# Sheet1.net
KiCad netlist of a schematic drawn in Altium Designer
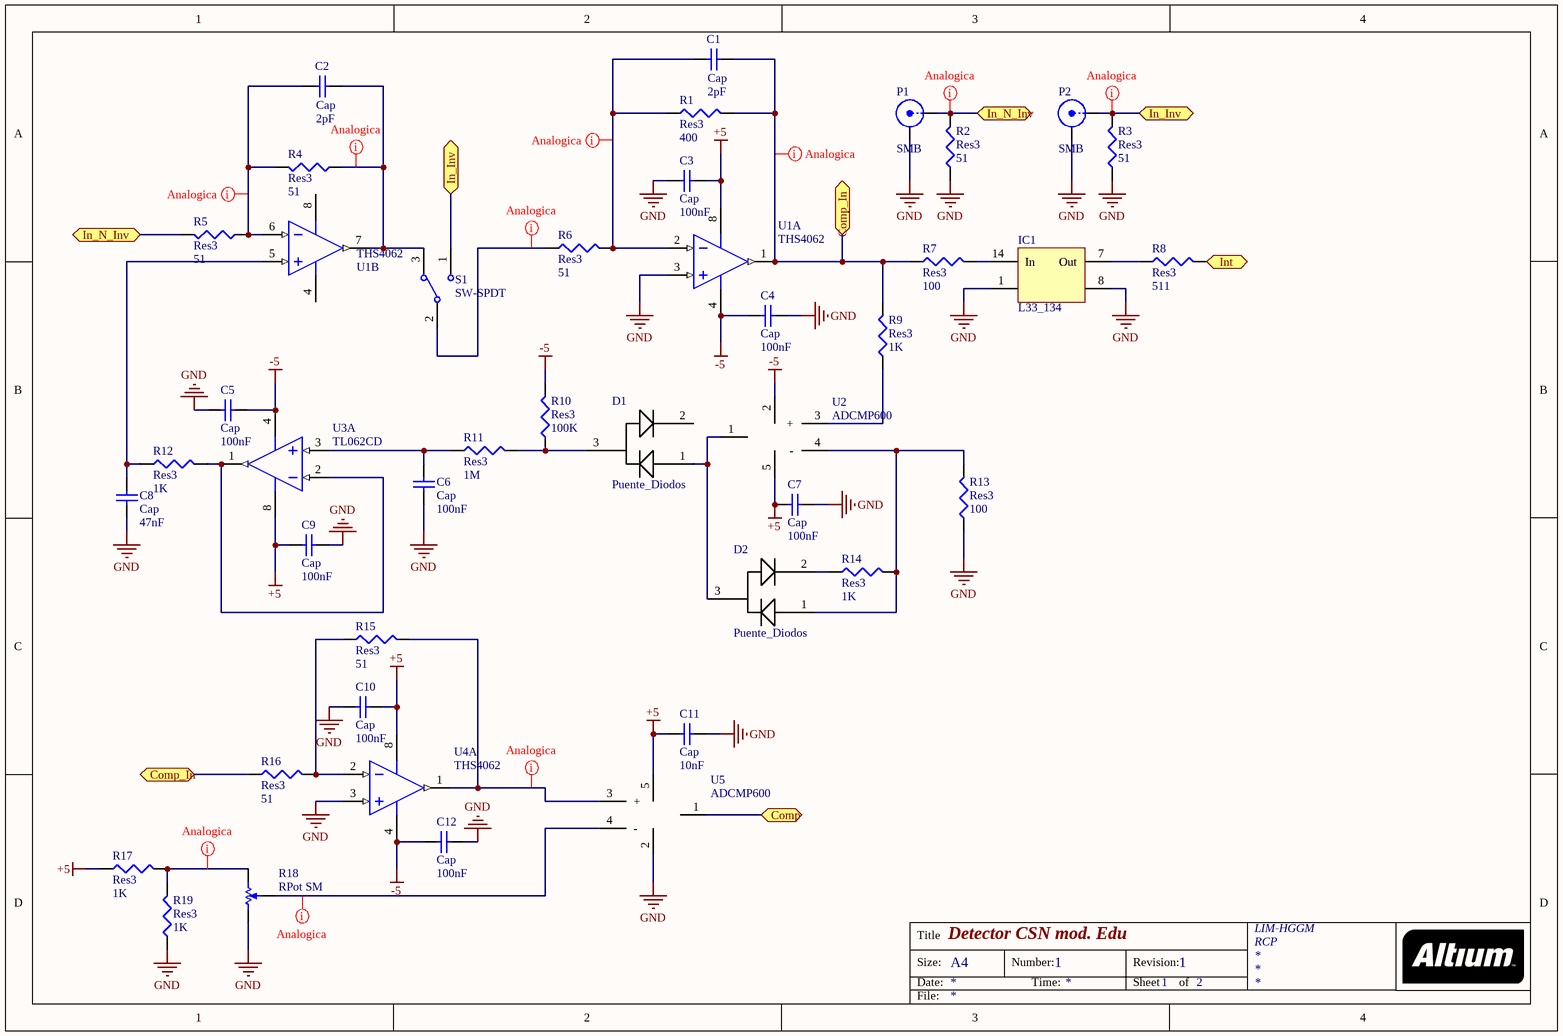
[diagram p0: Sheet1.SchDoc]

(export (version "E")
  (design (tool "Eeschema 10.0.6"))
  (components
    (comp (ref "C1")
      (value "Cap")
      (footprint "6-0805_N")
      (description "Capacitor")
      (fields (field (name "ALTIUM_VALUE") "2pF") (field (name "PUBLISHER") "Altium Limited"))
      (libsource (lib "Miscellaneous Devices") (part "Cap"))
    )
    (comp (ref "C2")
      (value "Cap")
      (footprint "6-0805_N")
      (description "Capacitor")
      (fields (field (name "ALTIUM_VALUE") "2pF") (field (name "PUBLISHER") "Altium Limited"))
      (libsource (lib "Miscellaneous Devices") (part "Cap"))
    )
    (comp (ref "C3")
      (value "Cap")
      (footprint "6-0805_N")
      (description "Capacitor")
      (fields (field (name "ALTIUM_VALUE") "100nF") (field (name "PUBLISHER") "Altium Limited"))
      (libsource (lib "Miscellaneous Devices") (part "Cap"))
    )
    (comp (ref "C4")
      (value "Cap")
      (footprint "6-0805_N")
      (description "Capacitor")
      (fields (field (name "ALTIUM_VALUE") "100nF") (field (name "PUBLISHER") "Altium Limited"))
      (libsource (lib "Miscellaneous Devices") (part "Cap"))
    )
    (comp (ref "C5")
      (value "Cap")
      (footprint "6-0805_N")
      (description "Capacitor")
      (fields (field (name "ALTIUM_VALUE") "100nF") (field (name "PUBLISHER") "Altium Limited"))
      (libsource (lib "Miscellaneous Devices") (part "Cap"))
    )
    (comp (ref "C6")
      (value "Cap")
      (footprint "6-0805_N")
      (description "Capacitor")
      (fields (field (name "ALTIUM_VALUE") "100nF") (field (name "PUBLISHER") "Altium Limited"))
      (libsource (lib "Miscellaneous Devices") (part "Cap"))
    )
    (comp (ref "C7")
      (value "Cap")
      (footprint "6-0805_N")
      (description "Capacitor")
      (fields (field (name "ALTIUM_VALUE") "100nF") (field (name "PUBLISHER") "Altium Limited"))
      (libsource (lib "Miscellaneous Devices") (part "Cap"))
    )
    (comp (ref "C8")
      (value "Cap")
      (footprint "6-0805_N")
      (description "Capacitor")
      (fields (field (name "ALTIUM_VALUE") "47nF") (field (name "PUBLISHER") "Altium Limited"))
      (libsource (lib "Miscellaneous Devices") (part "Cap"))
    )
    (comp (ref "C9")
      (value "Cap")
      (footprint "6-0805_N")
      (description "Capacitor")
      (fields (field (name "ALTIUM_VALUE") "100nF") (field (name "PUBLISHER") "Altium Limited"))
      (libsource (lib "Miscellaneous Devices") (part "Cap"))
    )
    (comp (ref "C10")
      (value "Cap")
      (footprint "6-0805_N")
      (description "Capacitor")
      (fields (field (name "ALTIUM_VALUE") "100nF") (field (name "PUBLISHER") "Altium Limited"))
      (libsource (lib "Miscellaneous Devices") (part "Cap"))
    )
    (comp (ref "C11")
      (value "Cap")
      (footprint "6-0805_N")
      (description "Capacitor")
      (fields (field (name "ALTIUM_VALUE") "10nF") (field (name "PUBLISHER") "Altium Limited"))
      (libsource (lib "Miscellaneous Devices") (part "Cap"))
    )
    (comp (ref "C12")
      (value "Cap")
      (footprint "6-0805_N")
      (description "Capacitor")
      (fields (field (name "ALTIUM_VALUE") "100nF") (field (name "PUBLISHER") "Altium Limited"))
      (libsource (lib "Miscellaneous Devices") (part "Cap"))
    )
    (comp (ref "D1")
      (value "Puente_Diodos")
      (footprint "SOT-23B_N")
      (libsource (lib "Schlib1") (part "Puente_Diodos"))
    )
    (comp (ref "D2")
      (value "Puente_Diodos")
      (footprint "SOT-23B_N")
      (libsource (lib "Schlib1") (part "Puente_Diodos"))
    )
    (comp (ref "IC1") (value "L33_134") (footprint "DIP14") (libsource (lib "Schlib1") (part "L33_134")))
    (comp (ref "P1")
      (value "SMB")
      (footprint "SMB_V-RJ45")
      (description "SMB Straight Connector")
      (fields (field (name "PUBLISHER") "Altium Limited"))
      (libsource (lib "Miscellaneous Connectors") (part "SMB"))
    )
    (comp (ref "P2")
      (value "SMB")
      (footprint "SMB_V-RJ45")
      (description "SMB Straight Connector")
      (fields (field (name "PUBLISHER") "Altium Limited"))
      (libsource (lib "Miscellaneous Connectors") (part "SMB"))
    )
    (comp (ref "R1")
      (value "Res3")
      (footprint "6-0805_N")
      (description "Resistor")
      (fields (field (name "ALTIUM_VALUE") "400") (field (name "PUBLISHER") "Altium Limited"))
      (libsource (lib "Miscellaneous Devices") (part "Res3"))
    )
    (comp (ref "R2")
      (value "Res3")
      (footprint "6-0805_N")
      (description "Resistor")
      (fields (field (name "ALTIUM_VALUE") "51") (field (name "PUBLISHER") "Altium Limited"))
      (libsource (lib "Miscellaneous Devices") (part "Res3"))
    )
    (comp (ref "R3")
      (value "Res3")
      (footprint "6-0805_N")
      (description "Resistor")
      (fields (field (name "ALTIUM_VALUE") "51") (field (name "PUBLISHER") "Altium Limited"))
      (libsource (lib "Miscellaneous Devices") (part "Res3"))
    )
    (comp (ref "R4")
      (value "Res3")
      (footprint "6-0805_N")
      (description "Resistor")
      (fields (field (name "ALTIUM_VALUE") "51") (field (name "PUBLISHER") "Altium Limited"))
      (libsource (lib "Miscellaneous Devices") (part "Res3"))
    )
    (comp (ref "R5")
      (value "Res3")
      (footprint "6-0805_N")
      (description "Resistor")
      (fields (field (name "ALTIUM_VALUE") "51") (field (name "PUBLISHER") "Altium Limited"))
      (libsource (lib "Miscellaneous Devices") (part "Res3"))
    )
    (comp (ref "R6")
      (value "Res3")
      (footprint "6-0805_N")
      (description "Resistor")
      (fields (field (name "ALTIUM_VALUE") "51") (field (name "PUBLISHER") "Altium Limited"))
      (libsource (lib "Miscellaneous Devices") (part "Res3"))
    )
    (comp (ref "R7")
      (value "Res3")
      (footprint "6-0805_N")
      (description "Resistor")
      (fields (field (name "ALTIUM_VALUE") "100") (field (name "PUBLISHER") "Altium Limited"))
      (libsource (lib "Miscellaneous Devices") (part "Res3"))
    )
    (comp (ref "R8")
      (value "Res3")
      (footprint "6-0805_N")
      (description "Resistor")
      (fields (field (name "ALTIUM_VALUE") "511") (field (name "PUBLISHER") "Altium Limited"))
      (libsource (lib "Miscellaneous Devices") (part "Res3"))
    )
    (comp (ref "R9")
      (value "Res3")
      (footprint "6-0805_N")
      (description "Resistor")
      (fields (field (name "ALTIUM_VALUE") "1K") (field (name "PUBLISHER") "Altium Limited"))
      (libsource (lib "Miscellaneous Devices") (part "Res3"))
    )
    (comp (ref "R10")
      (value "Res3")
      (footprint "6-0805_N")
      (description "Resistor")
      (fields (field (name "ALTIUM_VALUE") "100K") (field (name "PUBLISHER") "Altium Limited"))
      (libsource (lib "Miscellaneous Devices") (part "Res3"))
    )
    (comp (ref "R11")
      (value "Res3")
      (footprint "6-0805_N")
      (description "Resistor")
      (fields (field (name "ALTIUM_VALUE") "1M") (field (name "PUBLISHER") "Altium Limited"))
      (libsource (lib "Miscellaneous Devices") (part "Res3"))
    )
    (comp (ref "R12")
      (value "Res3")
      (footprint "6-0805_N")
      (description "Resistor")
      (fields (field (name "ALTIUM_VALUE") "1K") (field (name "PUBLISHER") "Altium Limited"))
      (libsource (lib "Miscellaneous Devices") (part "Res3"))
    )
    (comp (ref "R13")
      (value "Res3")
      (footprint "6-0805_N")
      (description "Resistor")
      (fields (field (name "ALTIUM_VALUE") "100") (field (name "PUBLISHER") "Altium Limited"))
      (libsource (lib "Miscellaneous Devices") (part "Res3"))
    )
    (comp (ref "R14")
      (value "Res3")
      (footprint "6-0805_N")
      (description "Resistor")
      (fields (field (name "ALTIUM_VALUE") "1K") (field (name "PUBLISHER") "Altium Limited"))
      (libsource (lib "Miscellaneous Devices") (part "Res3"))
    )
    (comp (ref "R15")
      (value "Res3")
      (footprint "6-0805_N")
      (description "Resistor")
      (fields (field (name "ALTIUM_VALUE") "51") (field (name "PUBLISHER") "Altium Limited"))
      (libsource (lib "Miscellaneous Devices") (part "Res3"))
    )
    (comp (ref "R16")
      (value "Res3")
      (footprint "6-0805_N")
      (description "Resistor")
      (fields (field (name "ALTIUM_VALUE") "51") (field (name "PUBLISHER") "Altium Limited"))
      (libsource (lib "Miscellaneous Devices") (part "Res3"))
    )
    (comp (ref "R17")
      (value "Res3")
      (footprint "6-0805_N")
      (description "Resistor")
      (fields (field (name "ALTIUM_VALUE") "1K") (field (name "PUBLISHER") "Altium Limited"))
      (libsource (lib "Miscellaneous Devices") (part "Res3"))
    )
    (comp (ref "R18")
      (value "RPot SM")
      (footprint "POT4MM-2")
      (description "Square Trimming Potentiometer")
      (fields (field (name "PUBLISHER") "Altium Limited"))
      (libsource (lib "Miscellaneous Devices") (part "RPot SM"))
    )
    (comp (ref "R19")
      (value "Res3")
      (footprint "6-0805_N")
      (description "Resistor")
      (fields (field (name "ALTIUM_VALUE") "1K") (field (name "PUBLISHER") "Altium Limited"))
      (libsource (lib "Miscellaneous Devices") (part "Res3"))
    )
    (comp (ref "S1")
      (value "SW-SPDT")
      (footprint "HDR1X3")
      (description "SPDT Subminiature Toggle Switch, Right Angle Mounting, Vertical Actuation")
      (fields (field (name "PUBLISHER") "Altium Limited"))
      (libsource (lib "Miscellaneous Devices") (part "SW-SPDT"))
    )
    (comp (ref "U1")
      (value "THS4062")
      (footprint "S8_N")
      (description "Low Cost Dual Video Amplifier")
      (fields (field (name "PUBLISHER") "Altium Limited"))
      (libsource (lib "LT Video Amplifier") (part "LT1253CS8"))
    )
    (comp (ref "U2") (value "ADCMP600") (footprint "SOT23-5_N") (libsource (lib "Schlib1") (part "ADCMP600")))
    (comp (ref "U3")
      (value "TL062CD")
      (footprint "S8_N")
      (description "Low Cost Dual Video Amplifier")
      (fields (field (name "PUBLISHER") "Altium Limited"))
      (libsource (lib "LT Video Amplifier") (part "LT1253CS8"))
    )
    (comp (ref "U4")
      (value "THS4062")
      (footprint "S8_N")
      (description "Low Cost Dual Video Amplifier")
      (fields (field (name "PUBLISHER") "Altium Limited"))
      (libsource (lib "LT Video Amplifier") (part "LT1253CS8"))
    )
    (comp (ref "U5") (value "ADCMP600") (footprint "SOT23-5_N") (libsource (lib "") (part "ADCMP600_1")))
  )
  (nets
    (net (code "1") (name "+5") (class "Default")
      (node (ref "C10") (pin "2") (pinfunction "2_2") (pintype "passive"))
      (node (ref "C11") (pin "1") (pinfunction "1_1") (pintype "passive"))
      (node (ref "C3") (pin "2") (pinfunction "2_2") (pintype "passive"))
      (node (ref "C7") (pin "1") (pinfunction "1_1") (pintype "passive"))
      (node (ref "C9") (pin "2") (pinfunction "2_2") (pintype "passive"))
      (node (ref "R17") (pin "1") (pinfunction "1_1") (pintype "passive"))
      (node (ref "U1") (pin "8") (pinfunction "V+_8") (pintype "power_in"))
      (node (ref "U2") (pin "5") (pintype "power_in"))
      (node (ref "U3") (pin "8") (pinfunction "V+_8") (pintype "power_in"))
      (node (ref "U4") (pin "8") (pinfunction "V+_8") (pintype "power_in"))
      (node (ref "U5") (pin "5") (pintype "power_in"))
    )
    (net (code "2") (name "-5") (class "Default")
      (node (ref "C12") (pin "1") (pinfunction "1_1") (pintype "passive"))
      (node (ref "C4") (pin "1") (pinfunction "1_1") (pintype "passive"))
      (node (ref "C5") (pin "1") (pinfunction "1_1") (pintype "passive"))
      (node (ref "R10") (pin "2") (pinfunction "2_2") (pintype "passive"))
      (node (ref "U1") (pin "4") (pinfunction "V-_4") (pintype "power_in"))
      (node (ref "U2") (pin "2") (pintype "power_in"))
      (node (ref "U3") (pin "4") (pinfunction "V-_4") (pintype "power_in"))
      (node (ref "U4") (pin "4") (pinfunction "V-_4") (pintype "power_in"))
    )
    (net (code "3") (name "/Comp") (class "Default") (node (ref "U5") (pin "1") (pintype "passive")))
    (net (code "4") (name "/Comp_In") (class "Default")
      (node (ref "C1") (pin "2") (pinfunction "2_2") (pintype "passive"))
      (node (ref "R1") (pin "2") (pinfunction "2_2") (pintype "passive"))
      (node (ref "R16") (pin "1") (pinfunction "1_1") (pintype "passive"))
      (node (ref "R7") (pin "1") (pinfunction "1_1") (pintype "passive"))
      (node (ref "R9") (pin "2") (pinfunction "2_2") (pintype "passive"))
      (node (ref "U1") (pin "1") (pinfunction "OUT_1") (pintype "output"))
    )
    (net (code "5") (name "/In_Inv") (class "Default")
      (node (ref "P2") (pin "1") (pinfunction "X_1") (pintype "passive"))
      (node (ref "R3") (pin "2") (pinfunction "2_2") (pintype "passive"))
      (node (ref "S1") (pin "1") (pinfunction "1_1") (pintype "passive"))
    )
    (net (code "6") (name "/In_N_Inv") (class "Default")
      (node (ref "P1") (pin "1") (pinfunction "X_1") (pintype "passive"))
      (node (ref "R2") (pin "2") (pinfunction "2_2") (pintype "passive"))
      (node (ref "R5") (pin "2") (pinfunction "2_2") (pintype "passive"))
    )
    (net (code "7") (name "/Int") (class "Default")
      (node (ref "R8") (pin "2") (pinfunction "2_2") (pintype "passive"))
    )
    (net (code "8") (name "GND") (class "Default")
      (node (ref "C10") (pin "1") (pinfunction "1_1") (pintype "passive"))
      (node (ref "C11") (pin "2") (pinfunction "2_2") (pintype "passive"))
      (node (ref "C12") (pin "2") (pinfunction "2_2") (pintype "passive"))
      (node (ref "C3") (pin "1") (pinfunction "1_1") (pintype "passive"))
      (node (ref "C4") (pin "2") (pinfunction "2_2") (pintype "passive"))
      (node (ref "C5") (pin "2") (pinfunction "2_2") (pintype "passive"))
      (node (ref "C6") (pin "2") (pinfunction "2_2") (pintype "passive"))
      (node (ref "C7") (pin "2") (pinfunction "2_2") (pintype "passive"))
      (node (ref "C8") (pin "2") (pinfunction "2_2") (pintype "passive"))
      (node (ref "C9") (pin "1") (pinfunction "1_1") (pintype "passive"))
      (node (ref "IC1") (pin "1") (pintype "passive"))
      (node (ref "IC1") (pin "8") (pintype "passive"))
      (node (ref "P1") (pin "2") (pinfunction "Y_2") (pintype "passive"))
      (node (ref "P2") (pin "2") (pinfunction "Y_2") (pintype "passive"))
      (node (ref "R13") (pin "1") (pinfunction "1_1") (pintype "passive"))
      (node (ref "R18") (pin "CCW") (pinfunction "-_CCW") (pintype "passive"))
      (node (ref "R19") (pin "1") (pinfunction "1_1") (pintype "passive"))
      (node (ref "R2") (pin "1") (pinfunction "1_1") (pintype "passive"))
      (node (ref "R3") (pin "1") (pinfunction "1_1") (pintype "passive"))
      (node (ref "U1") (pin "3") (pinfunction "IN+_3") (pintype "input"))
      (node (ref "U4") (pin "3") (pinfunction "IN+_3") (pintype "input"))
      (node (ref "U5") (pin "2") (pintype "power_in"))
    )
    (net (code "9") (name "Net-(D1-Pad1)") (class "Default")
      (node (ref "D1") (pin "1") (pintype "passive"))
      (node (ref "D2") (pin "3") (pintype "passive"))
      (node (ref "U2") (pin "1") (pintype "passive"))
    )
    (net (code "10") (name "Net-(D1-Pad3)") (class "Default")
      (node (ref "D1") (pin "3") (pintype "passive"))
      (node (ref "R10") (pin "1") (pinfunction "1_1") (pintype "passive"))
      (node (ref "R11") (pin "2") (pinfunction "2_2") (pintype "passive"))
    )
    (net (code "11") (name "Net-(D2-Pad2)") (class "Default")
      (node (ref "D2") (pin "2") (pintype "passive"))
      (node (ref "R14") (pin "1") (pinfunction "1_1") (pintype "passive"))
    )
    (net (code "12") (name "Net-(IC1-In)") (class "Default")
      (node (ref "IC1") (pin "14") (pinfunction "In_14") (pintype "passive"))
      (node (ref "R7") (pin "2") (pinfunction "2_2") (pintype "passive"))
    )
    (net (code "13") (name "Net-(IC1-Out)") (class "Default")
      (node (ref "IC1") (pin "7") (pinfunction "Out_7") (pintype "passive"))
      (node (ref "R8") (pin "1") (pinfunction "1_1") (pintype "passive"))
    )
    (net (code "14") (name "Net-(R6-Pad1)") (class "Default")
      (node (ref "R6") (pin "1") (pinfunction "1_1") (pintype "passive"))
      (node (ref "S1") (pin "2") (pinfunction "2_2") (pintype "passive"))
    )
    (net (code "15") (name "Net-(R18-+)") (class "Default")
      (node (ref "R17") (pin "2") (pinfunction "2_2") (pintype "passive"))
      (node (ref "R18") (pin "CW") (pinfunction "+_CW") (pintype "passive"))
      (node (ref "R19") (pin "2") (pinfunction "2_2") (pintype "passive"))
    )
    (net (code "16") (name "Net-(U1A-IN-)") (class "Default")
      (node (ref "C1") (pin "1") (pinfunction "1_1") (pintype "passive"))
      (node (ref "R1") (pin "1") (pinfunction "1_1") (pintype "passive"))
      (node (ref "R6") (pin "2") (pinfunction "2_2") (pintype "passive"))
      (node (ref "U1") (pin "2") (pinfunction "IN-_2") (pintype "input"))
    )
    (net (code "17") (name "Net-(U1B-IN+)") (class "Default")
      (node (ref "C8") (pin "1") (pinfunction "1_1") (pintype "passive"))
      (node (ref "R12") (pin "1") (pinfunction "1_1") (pintype "passive"))
      (node (ref "U1") (pin "5") (pinfunction "IN+_5") (pintype "input"))
    )
    (net (code "18") (name "Net-(U1B-IN-)") (class "Default")
      (node (ref "C2") (pin "1") (pinfunction "1_1") (pintype "passive"))
      (node (ref "R4") (pin "2") (pinfunction "2_2") (pintype "passive"))
      (node (ref "R5") (pin "1") (pinfunction "1_1") (pintype "passive"))
      (node (ref "U1") (pin "6") (pinfunction "IN-_6") (pintype "input"))
    )
    (net (code "19") (name "Net-(U1B-OUT)") (class "Default")
      (node (ref "C2") (pin "2") (pinfunction "2_2") (pintype "passive"))
      (node (ref "R4") (pin "1") (pinfunction "1_1") (pintype "passive"))
      (node (ref "S1") (pin "3") (pinfunction "3_3") (pintype "passive"))
      (node (ref "U1") (pin "7") (pinfunction "OUT_7") (pintype "output"))
    )
    (net (code "20") (name "Net-(U2-+)") (class "Default")
      (node (ref "R9") (pin "1") (pinfunction "1_1") (pintype "passive"))
      (node (ref "U2") (pin "3") (pinfunction "+_3") (pintype "passive"))
    )
    (net (code "21") (name "Net-(U2--)") (class "Default")
      (node (ref "D2") (pin "1") (pintype "passive"))
      (node (ref "R13") (pin "2") (pinfunction "2_2") (pintype "passive"))
      (node (ref "R14") (pin "2") (pinfunction "2_2") (pintype "passive"))
      (node (ref "U2") (pin "4") (pinfunction "-_4") (pintype "passive"))
    )
    (net (code "22") (name "Net-(U3A-IN+)") (class "Default")
      (node (ref "C6") (pin "1") (pinfunction "1_1") (pintype "passive"))
      (node (ref "R11") (pin "1") (pinfunction "1_1") (pintype "passive"))
      (node (ref "U3") (pin "3") (pinfunction "IN+_3") (pintype "input"))
    )
    (net (code "23") (name "Net-(U3A-IN-)") (class "Default")
      (node (ref "R12") (pin "2") (pinfunction "2_2") (pintype "passive"))
      (node (ref "U3") (pin "1") (pinfunction "OUT_1") (pintype "output"))
      (node (ref "U3") (pin "2") (pinfunction "IN-_2") (pintype "input"))
    )
    (net (code "24") (name "Net-(U4A-IN-)") (class "Default")
      (node (ref "R15") (pin "1") (pinfunction "1_1") (pintype "passive"))
      (node (ref "R16") (pin "2") (pinfunction "2_2") (pintype "passive"))
      (node (ref "U4") (pin "2") (pinfunction "IN-_2") (pintype "input"))
    )
    (net (code "25") (name "Net-(U4A-OUT)") (class "Default")
      (node (ref "R15") (pin "2") (pinfunction "2_2") (pintype "passive"))
      (node (ref "U4") (pin "1") (pinfunction "OUT_1") (pintype "output"))
      (node (ref "U5") (pin "3") (pinfunction "+_3") (pintype "passive"))
    )
    (net (code "26") (name "Net-(U5--)") (class "Default")
      (node (ref "R18") (pin "W") (pinfunction "W_W") (pintype "passive"))
      (node (ref "U5") (pin "4") (pinfunction "-_4") (pintype "passive"))
    )
    (net (code "27") (name "unconnected-(D1-Pad2)") (class "Default")
      (node (ref "D1") (pin "2") (pintype "passive"))
    )
    (net (code "28") (name "unconnected-(U1B-V+-Pad8)") (class "Default")
      (node (ref "U1") (pin "8") (pinfunction "V+_8") (pintype "power_in"))
    )
    (net (code "29") (name "unconnected-(U1B-V--Pad4)") (class "Default")
      (node (ref "U1") (pin "4") (pinfunction "V-_4") (pintype "power_in"))
    )
  )
)
